# LPC1100_dev.net
KiCad netlist of a schematic drawn in EAGLE
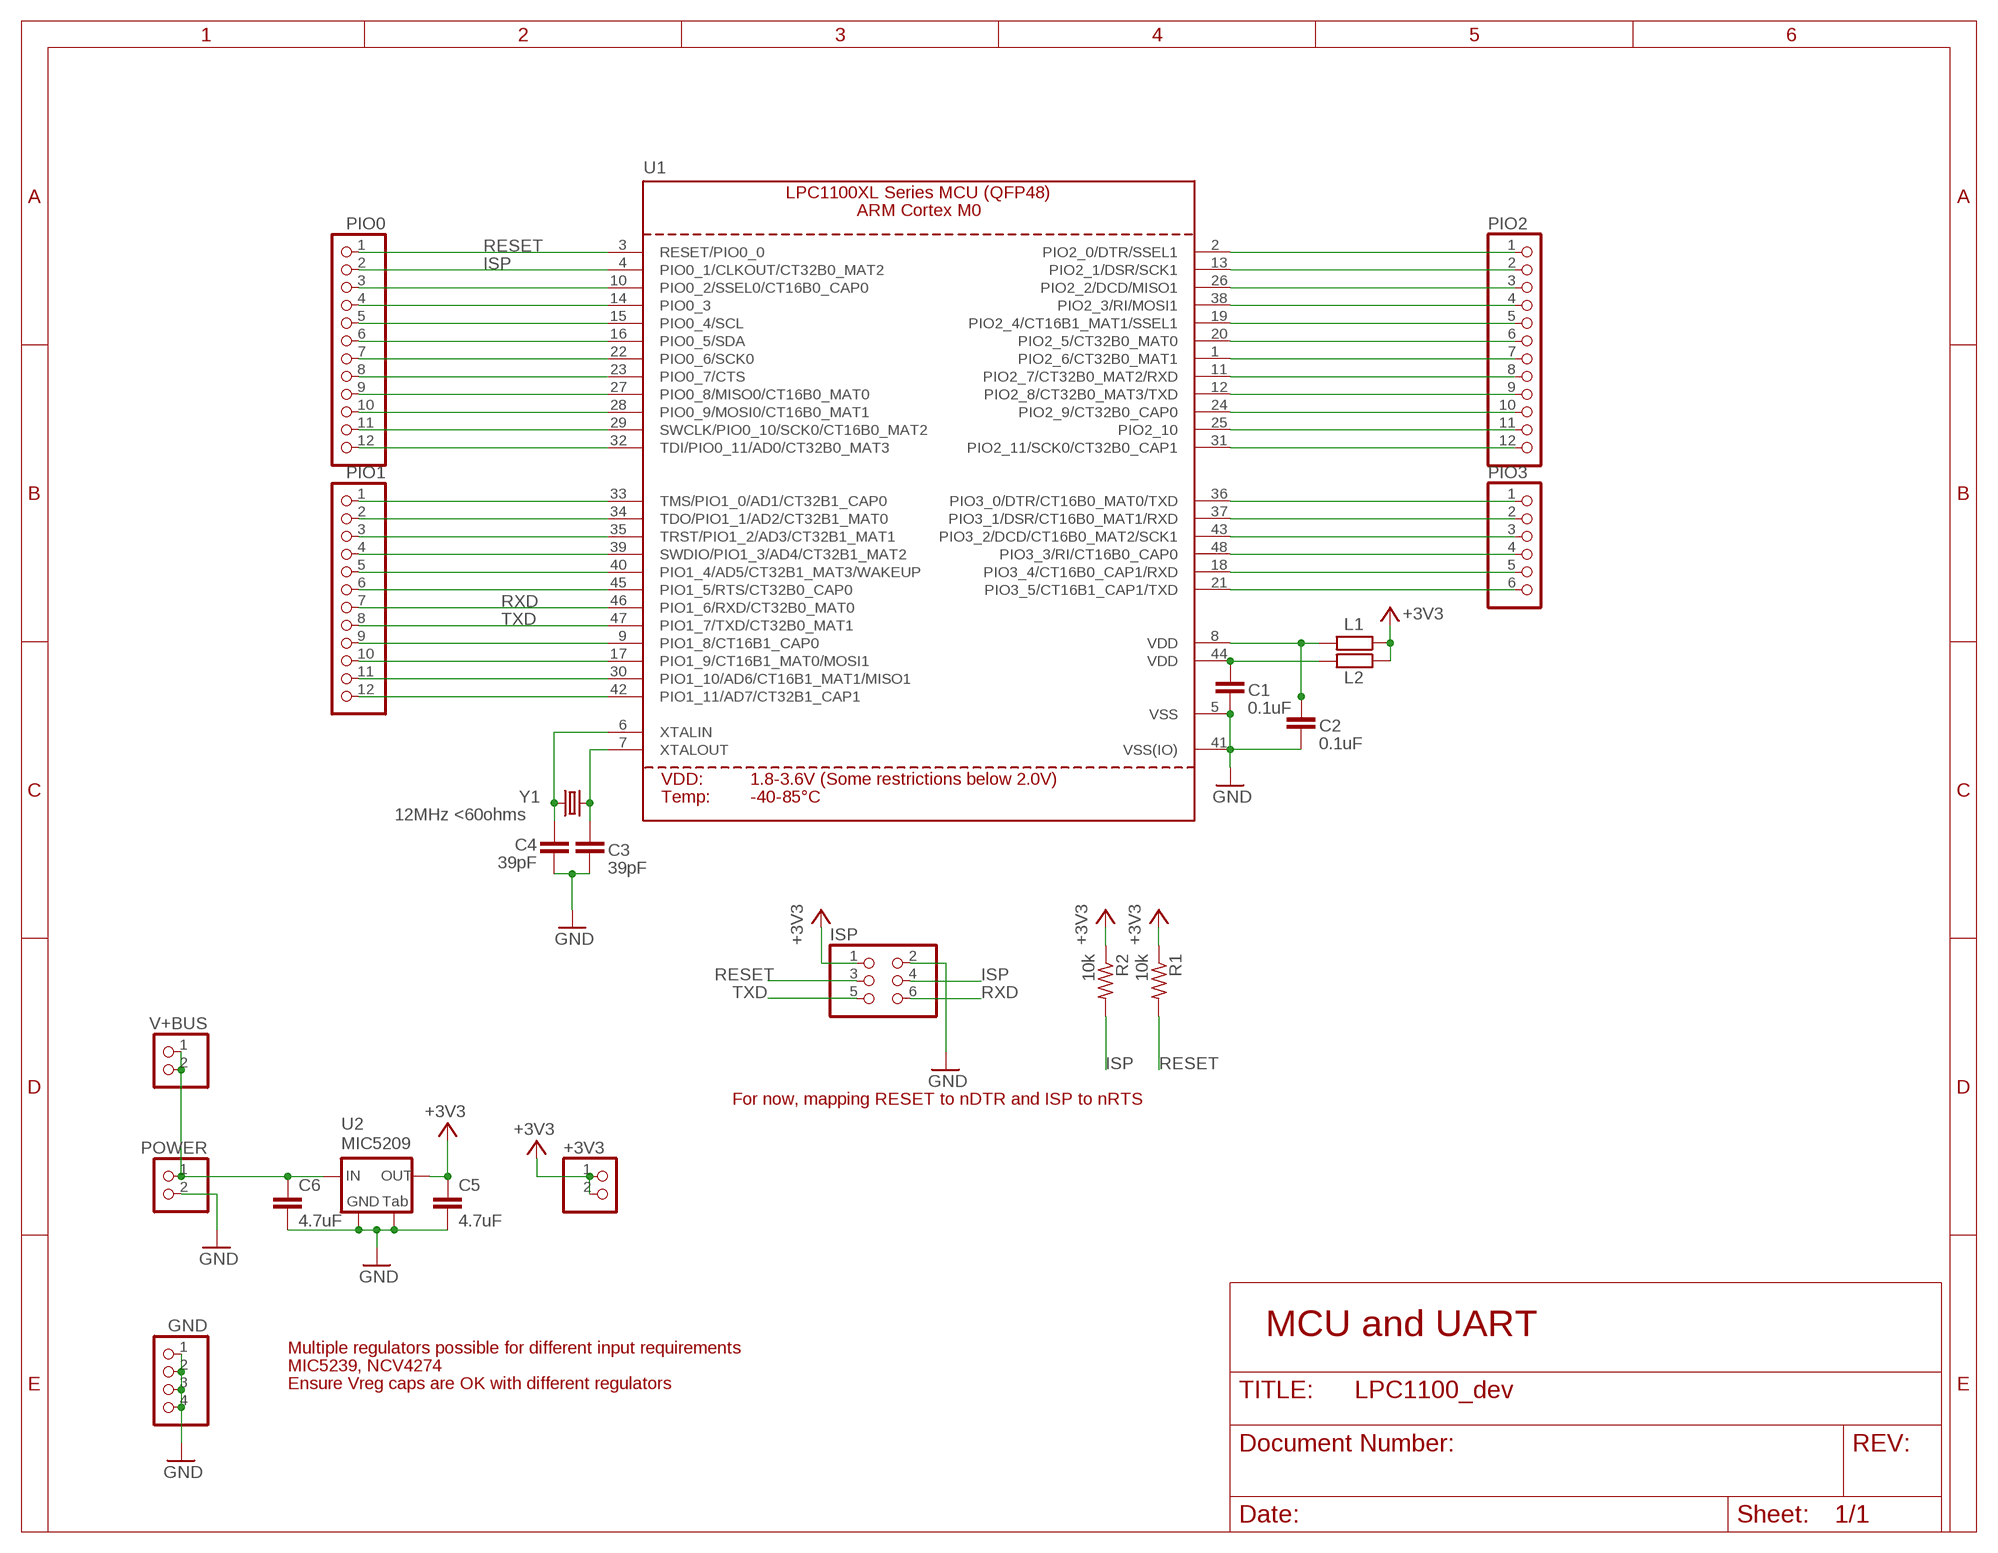
[diagram p0: schematic, sheet 1]

(export (version "E")
  (design (tool "Eeschema 10.0.6"))
  (components
    (comp (ref "+3V3")
      (value "PINHD-1X2")
      (footprint "eagle-import:1X02")
      (libsource (lib "eagle-import") (part "PINHD-1X2"))
    )
    (comp (ref "C1")
      (value "0.1uF")
      (footprint "eagle-import:C0603")
      (libsource (lib "eagle-import") (part "C-EUC0603"))
    )
    (comp (ref "C2")
      (value "0.1uF")
      (footprint "eagle-import:C0603")
      (libsource (lib "eagle-import") (part "C-EUC0603"))
    )
    (comp (ref "C3")
      (value "39pF")
      (footprint "eagle-import:C0603")
      (libsource (lib "eagle-import") (part "C-EUC0603"))
    )
    (comp (ref "C4")
      (value "39pF")
      (footprint "eagle-import:C0603")
      (libsource (lib "eagle-import") (part "C-EUC0603"))
    )
    (comp (ref "C5")
      (value "4.7uF")
      (footprint "eagle-import:C1210")
      (libsource (lib "eagle-import") (part "C-EUC1210"))
    )
    (comp (ref "C6")
      (value "4.7uF")
      (footprint "eagle-import:C1210")
      (libsource (lib "eagle-import") (part "C-EUC1210"))
    )
    (comp (ref "GND")
      (value "PINHD-1X4")
      (footprint "eagle-import:1X04")
      (libsource (lib "eagle-import") (part "PINHD-1X4"))
    )
    (comp (ref "ISP")
      (value "PINHD-2X3")
      (footprint "eagle-import:2X03")
      (libsource (lib "eagle-import") (part "PINHD-2X3"))
    )
    (comp (ref "L1")
      (value "R-EU_R0603")
      (footprint "eagle-import:R0603")
      (libsource (lib "eagle-import") (part "R-EU_R0603"))
    )
    (comp (ref "L2")
      (value "R-EU_R0603")
      (footprint "eagle-import:R0603")
      (libsource (lib "eagle-import") (part "R-EU_R0603"))
    )
    (comp (ref "PIO0")
      (value "PINHD-1X12")
      (footprint "eagle-import:1X12")
      (libsource (lib "eagle-import") (part "PINHD-1X12"))
    )
    (comp (ref "PIO1")
      (value "PINHD-1X12")
      (footprint "eagle-import:1X12")
      (libsource (lib "eagle-import") (part "PINHD-1X12"))
    )
    (comp (ref "PIO2")
      (value "PINHD-1X12")
      (footprint "eagle-import:1X12")
      (libsource (lib "eagle-import") (part "PINHD-1X12"))
    )
    (comp (ref "PIO3")
      (value "PINHD-1X6")
      (footprint "eagle-import:1X06")
      (libsource (lib "eagle-import") (part "PINHD-1X6"))
    )
    (comp (ref "POWER")
      (value "PINHD-1X2")
      (footprint "eagle-import:1X02")
      (libsource (lib "eagle-import") (part "PINHD-1X2"))
    )
    (comp (ref "R1")
      (value "10k")
      (footprint "eagle-import:R0603")
      (libsource (lib "eagle-import") (part "R-US_R0603"))
    )
    (comp (ref "R2")
      (value "10k")
      (footprint "eagle-import:R0603")
      (libsource (lib "eagle-import") (part "R-US_R0603"))
    )
    (comp (ref "U1")
      (value "LPC1113/4/5_QFP48_XLSERIES")
      (footprint "eagle-import:LQFP48")
      (libsource (lib "eagle-import") (part "LPC1113/4/5_QFP48_XLSERIES"))
    )
    (comp (ref "U2")
      (value "MIC5209")
      (footprint "eagle-import:SOT223")
      (libsource (lib "eagle-import") (part "MIC5239"))
    )
    (comp (ref "V+BUS")
      (value "PINHD-1X2")
      (footprint "eagle-import:1X02")
      (libsource (lib "eagle-import") (part "PINHD-1X2"))
    )
    (comp (ref "Y1")
      (value "12MHz <60ohms")
      (footprint "eagle-import:HC49_S")
      (libsource (lib "eagle-import") (part "CRYSTALHC49S"))
    )
  )
  (nets
    (net (code "1") (name "+3V3") (class "Default")
      (node (ref "+3V3") (pin "1") (pinfunction "1_1") (pintype "passive"))
      (node (ref "+3V3") (pin "2") (pinfunction "2_2") (pintype "passive"))
      (node (ref "C5") (pin "1") (pinfunction "1_1") (pintype "passive"))
      (node (ref "ISP") (pin "1") (pinfunction "1_1") (pintype "passive"))
      (node (ref "L1") (pin "1") (pinfunction "1_1") (pintype "passive"))
      (node (ref "L2") (pin "1") (pinfunction "1_1") (pintype "passive"))
      (node (ref "R1") (pin "1") (pinfunction "1_1") (pintype "passive"))
      (node (ref "R2") (pin "1") (pinfunction "1_1") (pintype "passive"))
      (node (ref "U2") (pin "3") (pinfunction "OUT_3") (pintype "power_in"))
    )
    (net (code "2") (name "/ISP") (class "Default")
      (node (ref "ISP") (pin "4") (pinfunction "4_4") (pintype "passive"))
      (node (ref "PIO0") (pin "2") (pinfunction "2_2") (pintype "passive"))
      (node (ref "R2") (pin "2") (pinfunction "2_2") (pintype "passive"))
      (node (ref "U1") (pin "4") (pinfunction "PIO0_1/CLKOUT/CT32B0_MAT2_4") (pintype "bidirectional"))
    )
    (net (code "3") (name "/RESET") (class "Default")
      (node (ref "ISP") (pin "3") (pinfunction "3_3") (pintype "passive"))
      (node (ref "PIO0") (pin "1") (pinfunction "1_1") (pintype "passive"))
      (node (ref "R1") (pin "2") (pinfunction "2_2") (pintype "passive"))
      (node (ref "U1") (pin "3") (pinfunction "RESET/PIO0_0_3") (pintype "bidirectional"))
    )
    (net (code "4") (name "/RXD") (class "Default")
      (node (ref "ISP") (pin "6") (pinfunction "6_6") (pintype "passive"))
      (node (ref "PIO1") (pin "7") (pinfunction "7_7") (pintype "passive"))
      (node (ref "U1") (pin "46") (pinfunction "PIO1_6/RXD/CT32B0_MAT0_46") (pintype "bidirectional"))
    )
    (net (code "5") (name "/TXD") (class "Default")
      (node (ref "ISP") (pin "5") (pinfunction "5_5") (pintype "passive"))
      (node (ref "PIO1") (pin "8") (pinfunction "8_8") (pintype "passive"))
      (node (ref "U1") (pin "47") (pinfunction "PIO1_7/TXD/CT32B0_MAT1_47") (pintype "bidirectional"))
    )
    (net (code "6") (name "GND") (class "Default")
      (node (ref "C1") (pin "2") (pinfunction "2_2") (pintype "passive"))
      (node (ref "C2") (pin "2") (pinfunction "2_2") (pintype "passive"))
      (node (ref "C3") (pin "2") (pinfunction "2_2") (pintype "passive"))
      (node (ref "C4") (pin "2") (pinfunction "2_2") (pintype "passive"))
      (node (ref "C5") (pin "2") (pinfunction "2_2") (pintype "passive"))
      (node (ref "C6") (pin "2") (pinfunction "2_2") (pintype "passive"))
      (node (ref "GND") (pin "1") (pinfunction "1_1") (pintype "passive"))
      (node (ref "GND") (pin "2") (pinfunction "2_2") (pintype "passive"))
      (node (ref "GND") (pin "3") (pinfunction "3_3") (pintype "passive"))
      (node (ref "GND") (pin "4") (pinfunction "4_4") (pintype "passive"))
      (node (ref "ISP") (pin "2") (pinfunction "2_2") (pintype "passive"))
      (node (ref "POWER") (pin "2") (pinfunction "2_2") (pintype "passive"))
      (node (ref "U1") (pin "41") (pinfunction "VSS(IO)_41") (pintype "power_in"))
      (node (ref "U1") (pin "5") (pinfunction "VSS_5") (pintype "power_in"))
      (node (ref "U2") (pin "2") (pinfunction "GND_2") (pintype "power_in"))
      (node (ref "U2") (pin "4") (pinfunction "TAB_4") (pintype "power_in"))
    )
    (net (code "7") (name "Net-(C1-Pad1)") (class "Default")
      (node (ref "C1") (pin "1") (pinfunction "1_1") (pintype "passive"))
      (node (ref "L2") (pin "2") (pinfunction "2_2") (pintype "passive"))
      (node (ref "U1") (pin "44") (pinfunction "VDD_44") (pintype "power_in"))
    )
    (net (code "8") (name "Net-(C2-Pad1)") (class "Default")
      (node (ref "C2") (pin "1") (pinfunction "1_1") (pintype "passive"))
      (node (ref "L1") (pin "2") (pinfunction "2_2") (pintype "passive"))
      (node (ref "U1") (pin "8") (pinfunction "VDD_8") (pintype "power_in"))
    )
    (net (code "9") (name "Net-(U1-PIO0_2{slash}SSEL0{slash}CT16B0_CAP0)") (class "Default")
      (node (ref "PIO0") (pin "3") (pinfunction "3_3") (pintype "passive"))
      (node (ref "U1") (pin "10") (pinfunction "PIO0_2/SSEL0/CT16B0_CAP0_10") (pintype "bidirectional"))
    )
    (net (code "10") (name "Net-(U1-PIO0_3)") (class "Default")
      (node (ref "PIO0") (pin "4") (pinfunction "4_4") (pintype "passive"))
      (node (ref "U1") (pin "14") (pinfunction "PIO0_3_14") (pintype "bidirectional"))
    )
    (net (code "11") (name "Net-(U1-PIO0_4{slash}SCL)") (class "Default")
      (node (ref "PIO0") (pin "5") (pinfunction "5_5") (pintype "passive"))
      (node (ref "U1") (pin "15") (pinfunction "PIO0_4/SCL_15") (pintype "bidirectional"))
    )
    (net (code "12") (name "Net-(U1-PIO0_5{slash}SDA)") (class "Default")
      (node (ref "PIO0") (pin "6") (pinfunction "6_6") (pintype "passive"))
      (node (ref "U1") (pin "16") (pinfunction "PIO0_5/SDA_16") (pintype "bidirectional"))
    )
    (net (code "13") (name "Net-(U1-PIO0_6{slash}SCK0)") (class "Default")
      (node (ref "PIO0") (pin "7") (pinfunction "7_7") (pintype "passive"))
      (node (ref "U1") (pin "22") (pinfunction "PIO0_6/SCK0_22") (pintype "bidirectional"))
    )
    (net (code "14") (name "Net-(U1-PIO0_7{slash}CTS)") (class "Default")
      (node (ref "PIO0") (pin "8") (pinfunction "8_8") (pintype "passive"))
      (node (ref "U1") (pin "23") (pinfunction "PIO0_7/CTS_23") (pintype "bidirectional"))
    )
    (net (code "15") (name "Net-(U1-PIO0_8{slash}MISO0{slash}CT16B0_MAT0)") (class "Default")
      (node (ref "PIO0") (pin "9") (pinfunction "9_9") (pintype "passive"))
      (node (ref "U1") (pin "27") (pinfunction "PIO0_8/MISO0/CT16B0_MAT0_27") (pintype "bidirectional"))
    )
    (net (code "16") (name "Net-(U1-PIO0_9{slash}MOSI0{slash}CT16B0_MAT1)") (class "Default")
      (node (ref "PIO0") (pin "10") (pinfunction "10_10") (pintype "passive"))
      (node (ref "U1") (pin "28") (pinfunction "PIO0_9/MOSI0/CT16B0_MAT1_28") (pintype "bidirectional"))
    )
    (net (code "17") (name "Net-(U1-PIO1_4{slash}AD5{slash}CT32B1_MAT3{slash}WAKEUP)") (class "Default")
      (node (ref "PIO1") (pin "5") (pinfunction "5_5") (pintype "passive"))
      (node (ref "U1") (pin "40") (pinfunction "PIO1_4/AD5/CT32B1_MAT3/WAKEUP_40") (pintype "bidirectional"))
    )
    (net (code "18") (name "Net-(U1-PIO1_5{slash}RTS{slash}CT32B0_CAP0)") (class "Default")
      (node (ref "PIO1") (pin "6") (pinfunction "6_6") (pintype "passive"))
      (node (ref "U1") (pin "45") (pinfunction "PIO1_5/RTS/CT32B0_CAP0_45") (pintype "bidirectional"))
    )
    (net (code "19") (name "Net-(U1-PIO1_8{slash}CT16B1_CAP0)") (class "Default")
      (node (ref "PIO1") (pin "9") (pinfunction "9_9") (pintype "passive"))
      (node (ref "U1") (pin "9") (pinfunction "PIO1_8/CT16B1_CAP0_9") (pintype "bidirectional"))
    )
    (net (code "20") (name "Net-(U1-PIO1_9{slash}CT16B1_MAT0{slash}MOSI1)") (class "Default")
      (node (ref "PIO1") (pin "10") (pinfunction "10_10") (pintype "passive"))
      (node (ref "U1") (pin "17") (pinfunction "PIO1_9/CT16B1_MAT0/MOSI1_17") (pintype "bidirectional"))
    )
    (net (code "21") (name "Net-(U1-PIO1_10{slash}AD6{slash}CT16B1_MAT1{slash}MISO1)") (class "Default")
      (node (ref "PIO1") (pin "11") (pinfunction "11_11") (pintype "passive"))
      (node (ref "U1") (pin "30") (pinfunction "PIO1_10/AD6/CT16B1_MAT1/MISO1_30") (pintype "bidirectional"))
    )
    (net (code "22") (name "Net-(U1-PIO1_11{slash}AD7{slash}CT32B1_CAP1)") (class "Default")
      (node (ref "PIO1") (pin "12") (pinfunction "12_12") (pintype "passive"))
      (node (ref "U1") (pin "42") (pinfunction "PIO1_11/AD7/CT32B1_CAP1_42") (pintype "bidirectional"))
    )
    (net (code "23") (name "Net-(U1-PIO2_0{slash}DTR{slash}SSEL1)") (class "Default")
      (node (ref "PIO2") (pin "1") (pinfunction "1_1") (pintype "passive"))
      (node (ref "U1") (pin "2") (pinfunction "PIO2_0/DTR/SSEL1_2") (pintype "bidirectional"))
    )
    (net (code "24") (name "Net-(U1-PIO2_1{slash}DSR{slash}SCK1)") (class "Default")
      (node (ref "PIO2") (pin "2") (pinfunction "2_2") (pintype "passive"))
      (node (ref "U1") (pin "13") (pinfunction "PIO2_1/DSR/SCK1_13") (pintype "bidirectional"))
    )
    (net (code "25") (name "Net-(U1-PIO2_2{slash}DCD{slash}MISO1)") (class "Default")
      (node (ref "PIO2") (pin "3") (pinfunction "3_3") (pintype "passive"))
      (node (ref "U1") (pin "26") (pinfunction "PIO2_2/DCD/MISO1_26") (pintype "bidirectional"))
    )
    (net (code "26") (name "Net-(U1-PIO2_3{slash}RI{slash}MOSI1)") (class "Default")
      (node (ref "PIO2") (pin "4") (pinfunction "4_4") (pintype "passive"))
      (node (ref "U1") (pin "38") (pinfunction "PIO2_3/RI/MOSI1_38") (pintype "bidirectional"))
    )
    (net (code "27") (name "Net-(U1-PIO2_4{slash}CT16B1_MAT1{slash}SSEL1)") (class "Default")
      (node (ref "PIO2") (pin "5") (pinfunction "5_5") (pintype "passive"))
      (node (ref "U1") (pin "19") (pinfunction "PIO2_4/CT16B1_MAT1/SSEL1_19") (pintype "bidirectional"))
    )
    (net (code "28") (name "Net-(U1-PIO2_5{slash}CT32B0_MAT0)") (class "Default")
      (node (ref "PIO2") (pin "6") (pinfunction "6_6") (pintype "passive"))
      (node (ref "U1") (pin "20") (pinfunction "PIO2_5/CT32B0_MAT0_20") (pintype "bidirectional"))
    )
    (net (code "29") (name "Net-(U1-PIO2_6{slash}CT32B0_MAT1)") (class "Default")
      (node (ref "PIO2") (pin "7") (pinfunction "7_7") (pintype "passive"))
      (node (ref "U1") (pin "1") (pinfunction "PIO2_6/CT32B0_MAT1_1") (pintype "bidirectional"))
    )
    (net (code "30") (name "Net-(U1-PIO2_7{slash}CT32B0_MAT2{slash}RXD)") (class "Default")
      (node (ref "PIO2") (pin "8") (pinfunction "8_8") (pintype "passive"))
      (node (ref "U1") (pin "11") (pinfunction "PIO2_7/CT32B0_MAT2/RXD_11") (pintype "bidirectional"))
    )
    (net (code "31") (name "Net-(U1-PIO2_8{slash}CT32B0_MAT3{slash}TXD)") (class "Default")
      (node (ref "PIO2") (pin "9") (pinfunction "9_9") (pintype "passive"))
      (node (ref "U1") (pin "12") (pinfunction "PIO2_8/CT32B0_MAT3/TXD_12") (pintype "bidirectional"))
    )
    (net (code "32") (name "Net-(U1-PIO2_9{slash}CT32B0_CAP0)") (class "Default")
      (node (ref "PIO2") (pin "10") (pinfunction "10_10") (pintype "passive"))
      (node (ref "U1") (pin "24") (pinfunction "PIO2_9/CT32B0_CAP0_24") (pintype "bidirectional"))
    )
    (net (code "33") (name "Net-(U1-PIO2_10)") (class "Default")
      (node (ref "PIO2") (pin "11") (pinfunction "11_11") (pintype "passive"))
      (node (ref "U1") (pin "25") (pinfunction "PIO2_10_25") (pintype "bidirectional"))
    )
    (net (code "34") (name "Net-(U1-PIO2_11{slash}SCK0{slash}CT32B0_CAP1)") (class "Default")
      (node (ref "PIO2") (pin "12") (pinfunction "12_12") (pintype "passive"))
      (node (ref "U1") (pin "31") (pinfunction "PIO2_11/SCK0/CT32B0_CAP1_31") (pintype "bidirectional"))
    )
    (net (code "35") (name "Net-(U1-PIO3_0{slash}DTR{slash}CT16B0_MAT0{slash}TXD)") (class "Default")
      (node (ref "PIO3") (pin "1") (pinfunction "1_1") (pintype "passive"))
      (node (ref "U1") (pin "36") (pinfunction "PIO3_0/DTR/CT16B0_MAT0/TXD_36") (pintype "bidirectional"))
    )
    (net (code "36") (name "Net-(U1-PIO3_1{slash}DSR{slash}CT16B0_MAT1{slash}RXD)") (class "Default")
      (node (ref "PIO3") (pin "2") (pinfunction "2_2") (pintype "passive"))
      (node (ref "U1") (pin "37") (pinfunction "PIO3_1/DSR/CT16B0_MAT1/RXD_37") (pintype "bidirectional"))
    )
    (net (code "37") (name "Net-(U1-PIO3_2{slash}DCD{slash}CT16B0_MAT2{slash}SCK1)") (class "Default")
      (node (ref "PIO3") (pin "3") (pinfunction "3_3") (pintype "passive"))
      (node (ref "U1") (pin "43") (pinfunction "PIO3_2/DCD/CT16B0_MAT2/SCK1_43") (pintype "bidirectional"))
    )
    (net (code "38") (name "Net-(U1-PIO3_3{slash}RI{slash}CT16B0_CAP0)") (class "Default")
      (node (ref "PIO3") (pin "4") (pinfunction "4_4") (pintype "passive"))
      (node (ref "U1") (pin "48") (pinfunction "PIO3_3/RI/CT16B0_CAP0_48") (pintype "bidirectional"))
    )
    (net (code "39") (name "Net-(U1-PIO3_4{slash}CT16B0_CAP1{slash}RXD)") (class "Default")
      (node (ref "PIO3") (pin "5") (pinfunction "5_5") (pintype "passive"))
      (node (ref "U1") (pin "18") (pinfunction "PIO3_4/CT16B0_CAP1/RXD_18") (pintype "bidirectional"))
    )
    (net (code "40") (name "Net-(U1-PIO3_5{slash}CT16B1_CAP1{slash}TXD)") (class "Default")
      (node (ref "PIO3") (pin "6") (pinfunction "6_6") (pintype "passive"))
      (node (ref "U1") (pin "21") (pinfunction "PIO3_5/CT16B1_CAP1/TXD_21") (pintype "bidirectional"))
    )
    (net (code "41") (name "Net-(U1-SWCLK{slash}PIO0_10{slash}SCK0{slash}CT16B0_MAT2)") (class "Default")
      (node (ref "PIO0") (pin "11") (pinfunction "11_11") (pintype "passive"))
      (node (ref "U1") (pin "29") (pinfunction "SWCLK/PIO0_10/SCK0/CT16B0_MAT2_29") (pintype "bidirectional"))
    )
    (net (code "42") (name "Net-(U1-SWDIO{slash}PIO1_3{slash}AD4{slash}CT32B1_MAT2)") (class "Default")
      (node (ref "PIO1") (pin "4") (pinfunction "4_4") (pintype "passive"))
      (node (ref "U1") (pin "39") (pinfunction "SWDIO/PIO1_3/AD4/CT32B1_MAT2_39") (pintype "bidirectional"))
    )
    (net (code "43") (name "Net-(U1-TDI{slash}PIO0_11{slash}AD0{slash}CT32B0_MAT3)") (class "Default")
      (node (ref "PIO0") (pin "12") (pinfunction "12_12") (pintype "passive"))
      (node (ref "U1") (pin "32") (pinfunction "TDI/PIO0_11/AD0/CT32B0_MAT3_32") (pintype "bidirectional"))
    )
    (net (code "44") (name "Net-(U1-TDO{slash}PIO1_1{slash}AD2{slash}CT32B1_MAT0)") (class "Default")
      (node (ref "PIO1") (pin "2") (pinfunction "2_2") (pintype "passive"))
      (node (ref "U1") (pin "34") (pinfunction "TDO/PIO1_1/AD2/CT32B1_MAT0_34") (pintype "bidirectional"))
    )
    (net (code "45") (name "Net-(U1-TMS{slash}PIO1_0{slash}AD1{slash}CT32B1_CAP0)") (class "Default")
      (node (ref "PIO1") (pin "1") (pinfunction "1_1") (pintype "passive"))
      (node (ref "U1") (pin "33") (pinfunction "TMS/PIO1_0/AD1/CT32B1_CAP0_33") (pintype "bidirectional"))
    )
    (net (code "46") (name "Net-(U1-TRST{slash}PIO1_2{slash}AD3{slash}CT32B1_MAT1)") (class "Default")
      (node (ref "PIO1") (pin "3") (pinfunction "3_3") (pintype "passive"))
      (node (ref "U1") (pin "35") (pinfunction "TRST/PIO1_2/AD3/CT32B1_MAT1_35") (pintype "bidirectional"))
    )
    (net (code "47") (name "Net-(U1-XTALIN)") (class "Default")
      (node (ref "C4") (pin "1") (pinfunction "1_1") (pintype "passive"))
      (node (ref "U1") (pin "6") (pinfunction "XTALIN_6") (pintype "input"))
      (node (ref "Y1") (pin "1") (pinfunction "1_1") (pintype "passive"))
    )
    (net (code "48") (name "Net-(U1-XTALOUT)") (class "Default")
      (node (ref "C3") (pin "1") (pinfunction "1_1") (pintype "passive"))
      (node (ref "U1") (pin "7") (pinfunction "XTALOUT_7") (pintype "output"))
      (node (ref "Y1") (pin "2") (pinfunction "2_2") (pintype "passive"))
    )
    (net (code "49") (name "Net-(U2-IN)") (class "Default")
      (node (ref "C6") (pin "1") (pinfunction "1_1") (pintype "passive"))
      (node (ref "POWER") (pin "1") (pinfunction "1_1") (pintype "passive"))
      (node (ref "U2") (pin "1") (pinfunction "IN_1") (pintype "power_in"))
      (node (ref "V+BUS") (pin "1") (pinfunction "1_1") (pintype "passive"))
      (node (ref "V+BUS") (pin "2") (pinfunction "2_2") (pintype "passive"))
    )
  )
)
